# plusz-end-card-with-turnstile-mezzanine.net
KiCad netlist of a schematic drawn in EAGLE
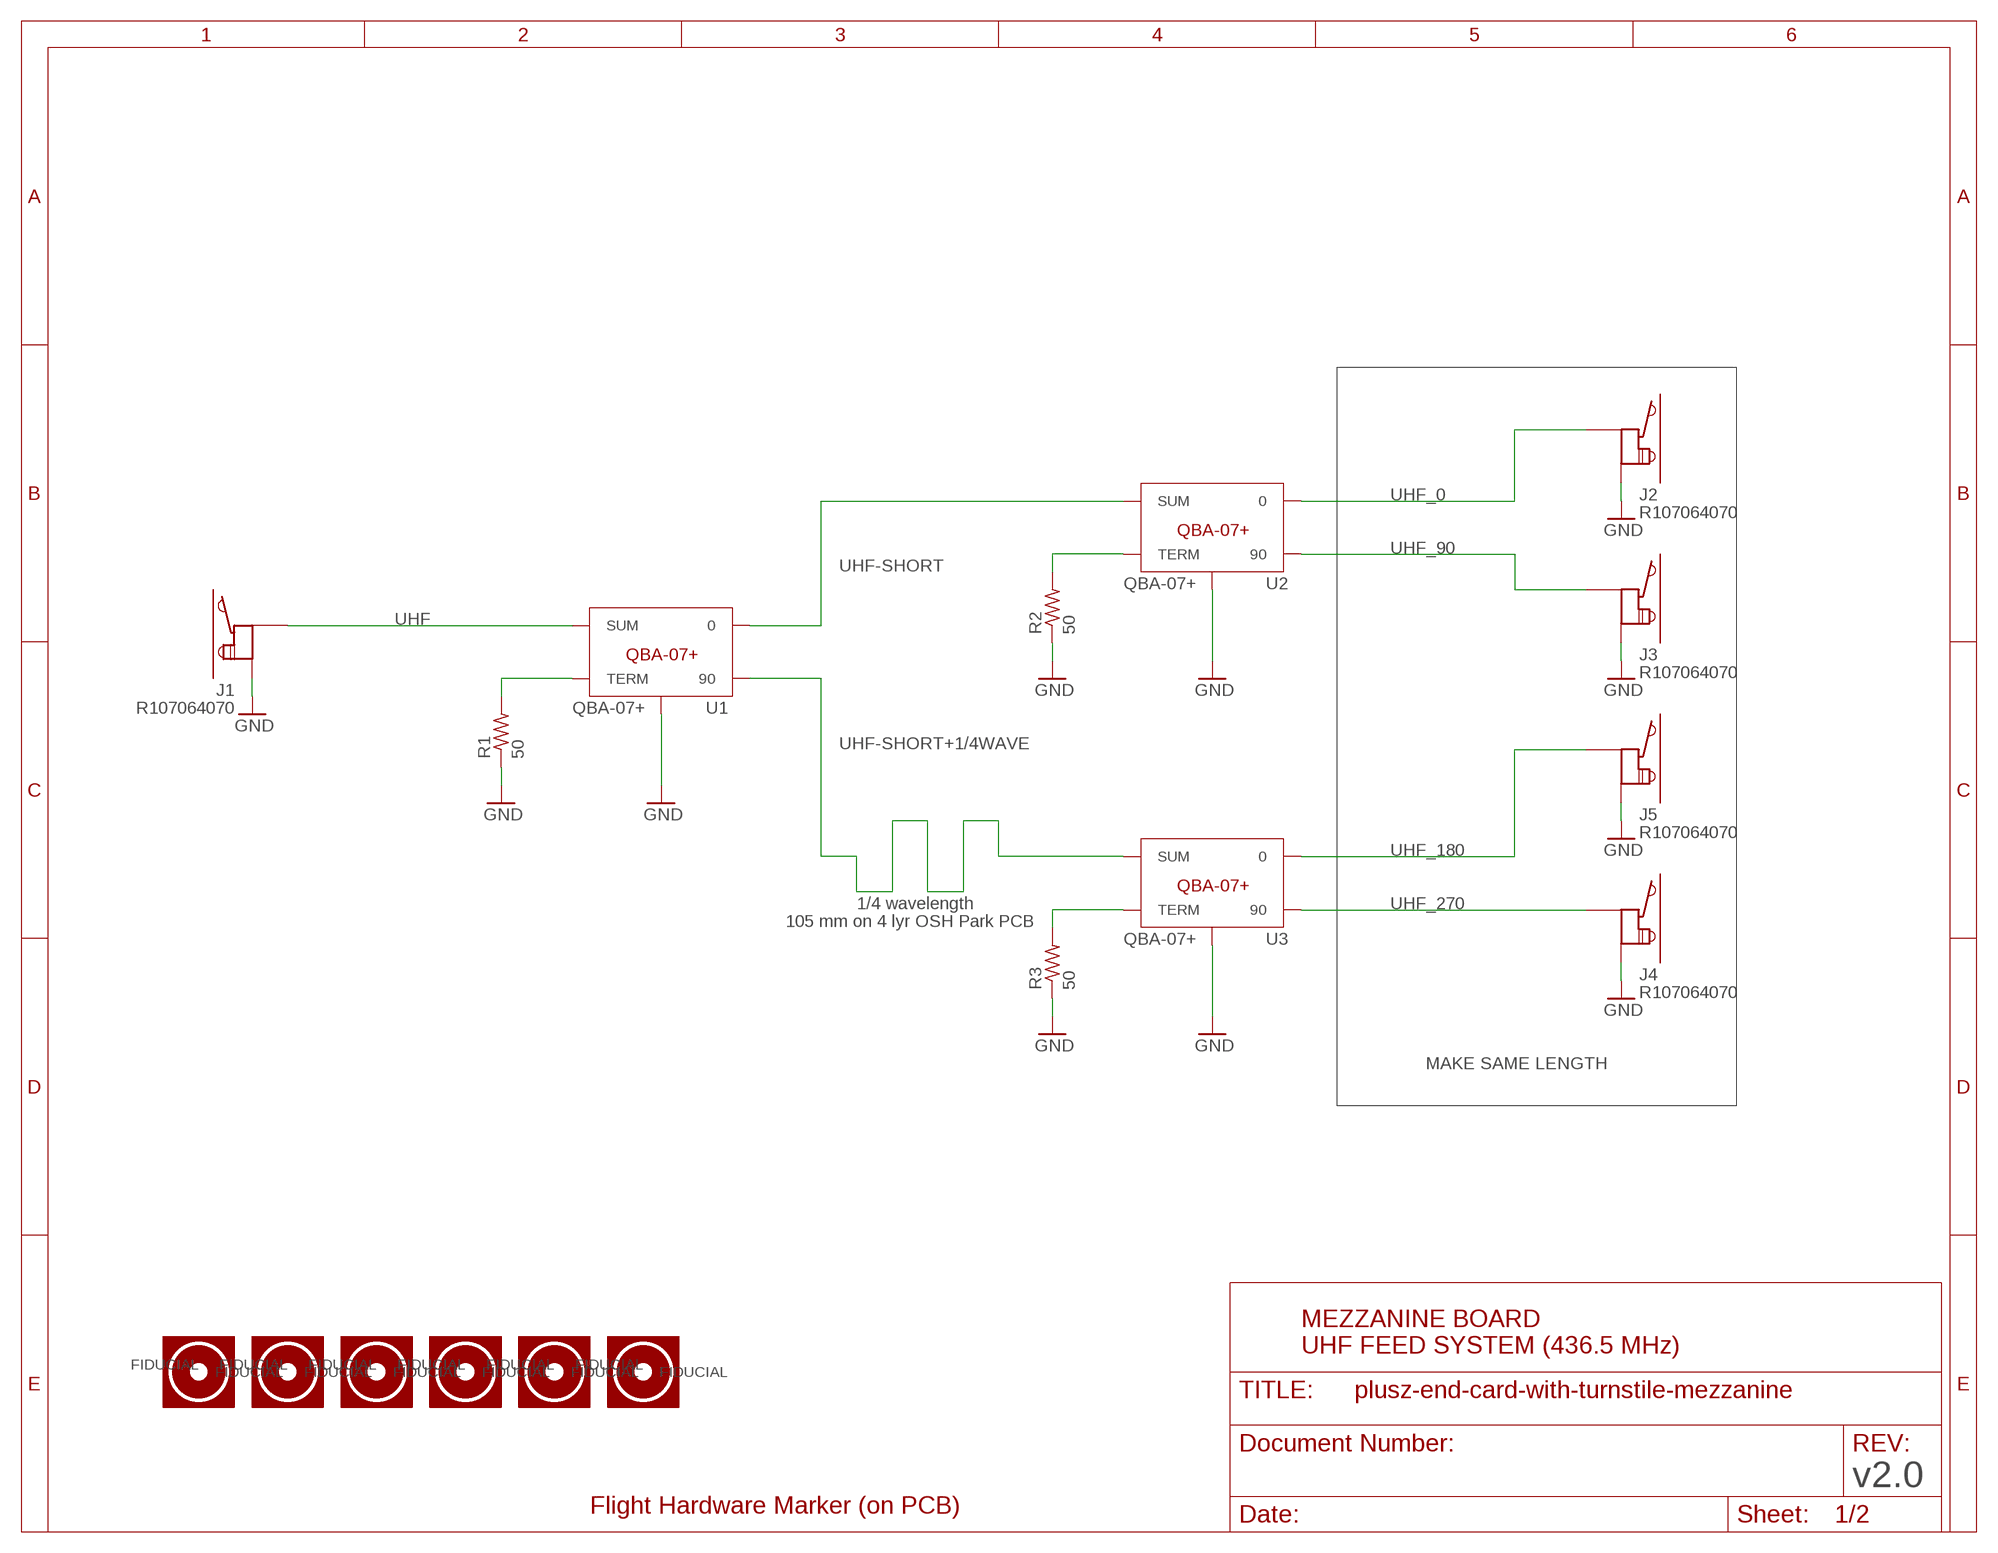
[diagram p0: schematic, sheet 1]
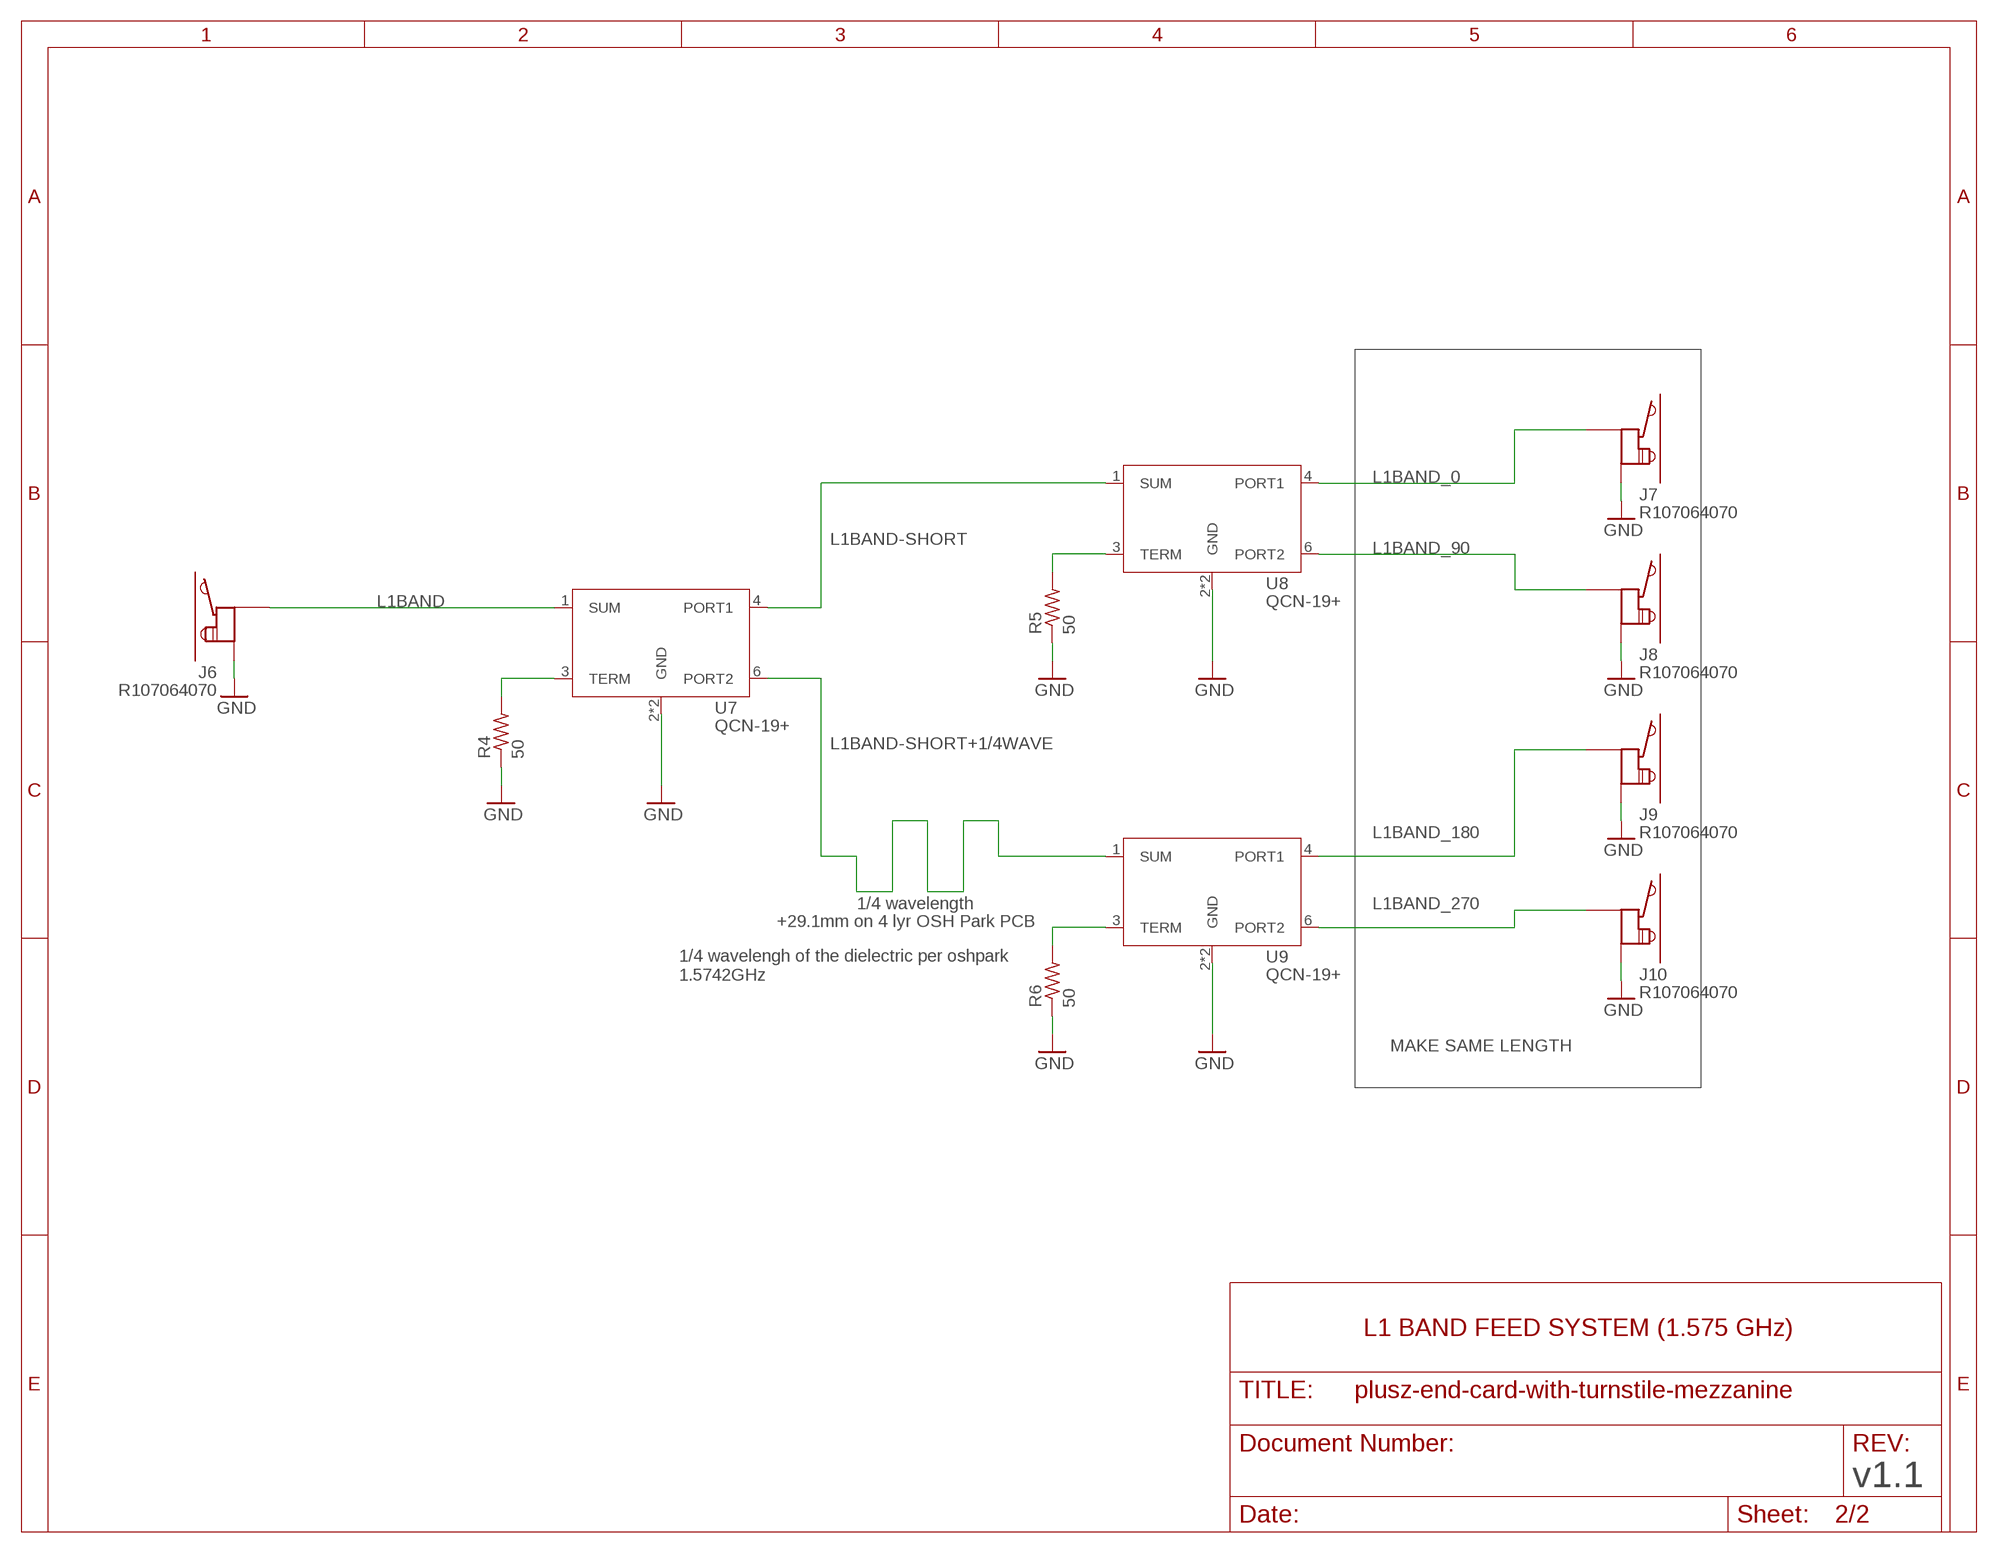
[diagram p1: schematic, sheet 2]

(export (version "E")
  (design (tool "Eeschema 10.0.6"))
  (components
    (comp (ref "J6")
      (value "R107064070")
      (footprint "eagle-import:R107064070_SOLDER")
      (fields (field (name "MFG") "Radiall"))
      (libsource (lib "eagle-import") (part "R107064070"))
    )
    (comp (ref "J7")
      (value "R107064070")
      (footprint "eagle-import:R107064070_SOLDER")
      (fields (field (name "MFG") "Radiall"))
      (libsource (lib "eagle-import") (part "R107064070"))
    )
    (comp (ref "J8")
      (value "R107064070")
      (footprint "eagle-import:R107064070_SOLDER")
      (fields (field (name "MFG") "Radiall"))
      (libsource (lib "eagle-import") (part "R107064070"))
    )
    (comp (ref "J9")
      (value "R107064070")
      (footprint "eagle-import:R107064070_SOLDER")
      (fields (field (name "MFG") "Radiall"))
      (libsource (lib "eagle-import") (part "R107064070"))
    )
    (comp (ref "J10")
      (value "R107064070")
      (footprint "eagle-import:R107064070_SOLDER")
      (fields (field (name "MFG") "Radiall"))
      (libsource (lib "eagle-import") (part "R107064070"))
    )
    (comp (ref "R4")
      (value "50")
      (footprint "eagle-import:.0603-C-NOSILK")
      (libsource (lib "eagle-import") (part "R-US_0603-C-NOSILK"))
    )
    (comp (ref "R5")
      (value "50")
      (footprint "eagle-import:.0603-C-NOSILK")
      (libsource (lib "eagle-import") (part "R-US_0603-C-NOSILK"))
    )
    (comp (ref "R6")
      (value "50")
      (footprint "eagle-import:.0603-C-NOSILK")
      (libsource (lib "eagle-import") (part "R-US_0603-C-NOSILK"))
    )
    (comp (ref "U7")
      (value "QCN-19+")
      (footprint "eagle-import:QCN-XXX+")
      (fields (field (name "MFG") "Mini-Circuits"))
      (libsource (lib "eagle-import") (part "QCN-XXX+"))
    )
    (comp (ref "U8")
      (value "QCN-19+")
      (footprint "eagle-import:QCN-XXX+")
      (fields (field (name "MFG") "Mini-Circuits"))
      (libsource (lib "eagle-import") (part "QCN-XXX+"))
    )
    (comp (ref "U9")
      (value "QCN-19+")
      (footprint "eagle-import:QCN-XXX+")
      (fields (field (name "MFG") "Mini-Circuits"))
      (libsource (lib "eagle-import") (part "QCN-XXX+"))
    )
    (comp (ref "FIDUCIAL1")
      (value "FIDUCIAL-1.0X2.0")
      (footprint "eagle-import:FIDUCIAL-1.0X2.0")
      (libsource (lib "eagle-import") (part "FIDUCIAL-1.0X2.0"))
    )
    (comp (ref "FIDUCIAL2")
      (value "FIDUCIAL-1.0X2.0")
      (footprint "eagle-import:FIDUCIAL-1.0X2.0")
      (libsource (lib "eagle-import") (part "FIDUCIAL-1.0X2.0"))
    )
    (comp (ref "FIDUCIAL3")
      (value "FIDUCIAL-1.0X2.0")
      (footprint "eagle-import:FIDUCIAL-1.0X2.0")
      (libsource (lib "eagle-import") (part "FIDUCIAL-1.0X2.0"))
    )
    (comp (ref "FIDUCIAL4")
      (value "FIDUCIAL-1.0X2.0")
      (footprint "eagle-import:FIDUCIAL-1.0X2.0")
      (libsource (lib "eagle-import") (part "FIDUCIAL-1.0X2.0"))
    )
    (comp (ref "FIDUCIAL6")
      (value "FIDUCIAL-1.0X2.0")
      (footprint "eagle-import:FIDUCIAL-1.0X2.0")
      (libsource (lib "eagle-import") (part "FIDUCIAL-1.0X2.0"))
    )
    (comp (ref "FIDUCIAL7")
      (value "FIDUCIAL-1.0X2.0")
      (footprint "eagle-import:FIDUCIAL-1.0X2.0")
      (libsource (lib "eagle-import") (part "FIDUCIAL-1.0X2.0"))
    )
    (comp (ref "J1")
      (value "R107064070")
      (footprint "eagle-import:R107064070_SOLDER")
      (fields (field (name "MFG") "Radiall"))
      (libsource (lib "eagle-import") (part "R107064070"))
    )
    (comp (ref "J2")
      (value "R107064070")
      (footprint "eagle-import:R107064070_SOLDER")
      (fields (field (name "MFG") "Radiall"))
      (libsource (lib "eagle-import") (part "R107064070"))
    )
    (comp (ref "J3")
      (value "R107064070")
      (footprint "eagle-import:R107064070_SOLDER")
      (fields (field (name "MFG") "Radiall"))
      (libsource (lib "eagle-import") (part "R107064070"))
    )
    (comp (ref "J4")
      (value "R107064070")
      (footprint "eagle-import:R107064070_SOLDER")
      (fields (field (name "MFG") "Radiall"))
      (libsource (lib "eagle-import") (part "R107064070"))
    )
    (comp (ref "J5")
      (value "R107064070")
      (footprint "eagle-import:R107064070_SOLDER")
      (fields (field (name "MFG") "Radiall"))
      (libsource (lib "eagle-import") (part "R107064070"))
    )
    (comp (ref "R1")
      (value "50")
      (footprint "eagle-import:.0603-C-NOSILK")
      (libsource (lib "eagle-import") (part "R-US_0603-C-NOSILK"))
    )
    (comp (ref "R2")
      (value "50")
      (footprint "eagle-import:.0603-C-NOSILK")
      (libsource (lib "eagle-import") (part "R-US_0603-C-NOSILK"))
    )
    (comp (ref "R3")
      (value "50")
      (footprint "eagle-import:.0603-C-NOSILK")
      (libsource (lib "eagle-import") (part "R-US_0603-C-NOSILK"))
    )
    (comp (ref "U$1")
      (value "FLIGHMARKERNEW")
      (footprint "eagle-import:FLIGHTMARKER_NEW_BOARDS")
      (libsource (lib "eagle-import") (part "FLIGHMARKERNEW"))
    )
    (comp (ref "U1")
      (value "QBA-07+")
      (footprint "eagle-import:QBA-07+")
      (libsource (lib "eagle-import") (part "QBA-07+"))
    )
    (comp (ref "U2")
      (value "QBA-07+")
      (footprint "eagle-import:QBA-07+")
      (libsource (lib "eagle-import") (part "QBA-07+"))
    )
    (comp (ref "U3")
      (value "QBA-07+")
      (footprint "eagle-import:QBA-07+")
      (libsource (lib "eagle-import") (part "QBA-07+"))
    )
  )
  (nets
    (net (code "1") (name "GND") (class "Default")
      (node (ref "J1") (pin "P$2") (pinfunction "P$2_P$2") (pintype "bidirectional"))
      (node (ref "J1") (pin "P$3") (pinfunction "P$2_P$3") (pintype "bidirectional"))
      (node (ref "J10") (pin "P$2") (pinfunction "P$2_P$2") (pintype "bidirectional"))
      (node (ref "J10") (pin "P$3") (pinfunction "P$2_P$3") (pintype "bidirectional"))
      (node (ref "J2") (pin "P$2") (pinfunction "P$2_P$2") (pintype "bidirectional"))
      (node (ref "J2") (pin "P$3") (pinfunction "P$2_P$3") (pintype "bidirectional"))
      (node (ref "J3") (pin "P$2") (pinfunction "P$2_P$2") (pintype "bidirectional"))
      (node (ref "J3") (pin "P$3") (pinfunction "P$2_P$3") (pintype "bidirectional"))
      (node (ref "J4") (pin "P$2") (pinfunction "P$2_P$2") (pintype "bidirectional"))
      (node (ref "J4") (pin "P$3") (pinfunction "P$2_P$3") (pintype "bidirectional"))
      (node (ref "J5") (pin "P$2") (pinfunction "P$2_P$2") (pintype "bidirectional"))
      (node (ref "J5") (pin "P$3") (pinfunction "P$2_P$3") (pintype "bidirectional"))
      (node (ref "J6") (pin "P$2") (pinfunction "P$2_P$2") (pintype "bidirectional"))
      (node (ref "J6") (pin "P$3") (pinfunction "P$2_P$3") (pintype "bidirectional"))
      (node (ref "J7") (pin "P$2") (pinfunction "P$2_P$2") (pintype "bidirectional"))
      (node (ref "J7") (pin "P$3") (pinfunction "P$2_P$3") (pintype "bidirectional"))
      (node (ref "J8") (pin "P$2") (pinfunction "P$2_P$2") (pintype "bidirectional"))
      (node (ref "J8") (pin "P$3") (pinfunction "P$2_P$3") (pintype "bidirectional"))
      (node (ref "J9") (pin "P$2") (pinfunction "P$2_P$2") (pintype "bidirectional"))
      (node (ref "J9") (pin "P$3") (pinfunction "P$2_P$3") (pintype "bidirectional"))
      (node (ref "R1") (pin "1") (pinfunction "1_1") (pintype "passive"))
      (node (ref "R2") (pin "1") (pinfunction "1_1") (pintype "passive"))
      (node (ref "R3") (pin "1") (pinfunction "1_1") (pintype "passive"))
      (node (ref "R4") (pin "1") (pinfunction "1_1") (pintype "passive"))
      (node (ref "R5") (pin "1") (pinfunction "1_1") (pintype "passive"))
      (node (ref "R6") (pin "1") (pinfunction "1_1") (pintype "passive"))
      (node (ref "U1") (pin "2") (pinfunction "GND_2") (pintype "power_in"))
      (node (ref "U1") (pin "3") (pinfunction "GND_3") (pintype "power_in"))
      (node (ref "U1") (pin "4") (pinfunction "GND_4") (pintype "power_in"))
      (node (ref "U1") (pin "7") (pinfunction "GND_7") (pintype "power_in"))
      (node (ref "U1") (pin "8") (pinfunction "GND_8") (pintype "power_in"))
      (node (ref "U1") (pin "9") (pinfunction "GND_9") (pintype "power_in"))
      (node (ref "U1") (pin "GND-NO-PAD") (pinfunction "GND_GND-NO-PAD") (pintype "power_in"))
      (node (ref "U2") (pin "2") (pinfunction "GND_2") (pintype "power_in"))
      (node (ref "U2") (pin "3") (pinfunction "GND_3") (pintype "power_in"))
      (node (ref "U2") (pin "4") (pinfunction "GND_4") (pintype "power_in"))
      (node (ref "U2") (pin "7") (pinfunction "GND_7") (pintype "power_in"))
      (node (ref "U2") (pin "8") (pinfunction "GND_8") (pintype "power_in"))
      (node (ref "U2") (pin "9") (pinfunction "GND_9") (pintype "power_in"))
      (node (ref "U2") (pin "GND-NO-PAD") (pinfunction "GND_GND-NO-PAD") (pintype "power_in"))
      (node (ref "U3") (pin "2") (pinfunction "GND_2") (pintype "power_in"))
      (node (ref "U3") (pin "3") (pinfunction "GND_3") (pintype "power_in"))
      (node (ref "U3") (pin "4") (pinfunction "GND_4") (pintype "power_in"))
      (node (ref "U3") (pin "7") (pinfunction "GND_7") (pintype "power_in"))
      (node (ref "U3") (pin "8") (pinfunction "GND_8") (pintype "power_in"))
      (node (ref "U3") (pin "9") (pinfunction "GND_9") (pintype "power_in"))
      (node (ref "U3") (pin "GND-NO-PAD") (pinfunction "GND_GND-NO-PAD") (pintype "power_in"))
      (node (ref "U7") (pin "2") (pinfunction "GND_2") (pintype "power_in"))
      (node (ref "U7") (pin "5") (pinfunction "GND_5") (pintype "power_in"))
      (node (ref "U8") (pin "2") (pinfunction "GND_2") (pintype "power_in"))
      (node (ref "U8") (pin "5") (pinfunction "GND_5") (pintype "power_in"))
      (node (ref "U9") (pin "2") (pinfunction "GND_2") (pintype "power_in"))
      (node (ref "U9") (pin "5") (pinfunction "GND_5") (pintype "power_in"))
    )
    (net (code "2") (name "L1BAND") (class "Default")
      (node (ref "J6") (pin "P$1") (pinfunction "P$1_P$1") (pintype "bidirectional"))
      (node (ref "U7") (pin "1") (pinfunction "SUM_1") (pintype "bidirectional"))
    )
    (net (code "3") (name "L1BAND-SHORT") (class "Default")
      (node (ref "U7") (pin "4") (pinfunction "PORT1_4") (pintype "bidirectional"))
      (node (ref "U8") (pin "1") (pinfunction "SUM_1") (pintype "bidirectional"))
    )
    (net (code "4") (name "L1BAND-SHORT+1{slash}4WAVE") (class "Default")
      (node (ref "U7") (pin "6") (pinfunction "PORT2_6") (pintype "bidirectional"))
      (node (ref "U9") (pin "1") (pinfunction "SUM_1") (pintype "bidirectional"))
    )
    (net (code "5") (name "L1BAND_0") (class "Default")
      (node (ref "J7") (pin "P$1") (pinfunction "P$1_P$1") (pintype "bidirectional"))
      (node (ref "U8") (pin "4") (pinfunction "PORT1_4") (pintype "bidirectional"))
    )
    (net (code "6") (name "L1BAND_90") (class "Default")
      (node (ref "J8") (pin "P$1") (pinfunction "P$1_P$1") (pintype "bidirectional"))
      (node (ref "U8") (pin "6") (pinfunction "PORT2_6") (pintype "bidirectional"))
    )
    (net (code "7") (name "L1BAND_180") (class "Default")
      (node (ref "J9") (pin "P$1") (pinfunction "P$1_P$1") (pintype "bidirectional"))
      (node (ref "U9") (pin "4") (pinfunction "PORT1_4") (pintype "bidirectional"))
    )
    (net (code "8") (name "L1BAND_270") (class "Default")
      (node (ref "J10") (pin "P$1") (pinfunction "P$1_P$1") (pintype "bidirectional"))
      (node (ref "U9") (pin "6") (pinfunction "PORT2_6") (pintype "bidirectional"))
    )
    (net (code "9") (name "Net-(U1-TERM)") (class "Default")
      (node (ref "R1") (pin "2") (pinfunction "2_2") (pintype "passive"))
      (node (ref "U1") (pin "5") (pinfunction "TERM_5") (pintype "passive"))
    )
    (net (code "10") (name "Net-(U2-TERM)") (class "Default")
      (node (ref "R2") (pin "2") (pinfunction "2_2") (pintype "passive"))
      (node (ref "U2") (pin "5") (pinfunction "TERM_5") (pintype "passive"))
    )
    (net (code "11") (name "Net-(U3-TERM)") (class "Default")
      (node (ref "R3") (pin "2") (pinfunction "2_2") (pintype "passive"))
      (node (ref "U3") (pin "5") (pinfunction "TERM_5") (pintype "passive"))
    )
    (net (code "12") (name "Net-(U7-TERM)") (class "Default")
      (node (ref "R4") (pin "2") (pinfunction "2_2") (pintype "passive"))
      (node (ref "U7") (pin "3") (pinfunction "TERM_3") (pintype "bidirectional"))
    )
    (net (code "13") (name "Net-(U8-TERM)") (class "Default")
      (node (ref "R5") (pin "2") (pinfunction "2_2") (pintype "passive"))
      (node (ref "U8") (pin "3") (pinfunction "TERM_3") (pintype "bidirectional"))
    )
    (net (code "14") (name "Net-(U9-TERM)") (class "Default")
      (node (ref "R6") (pin "2") (pinfunction "2_2") (pintype "passive"))
      (node (ref "U9") (pin "3") (pinfunction "TERM_3") (pintype "bidirectional"))
    )
    (net (code "15") (name "UHF") (class "Default")
      (node (ref "J1") (pin "P$1") (pinfunction "P$1_P$1") (pintype "bidirectional"))
      (node (ref "U1") (pin "1") (pinfunction "SUM_1") (pintype "passive"))
    )
    (net (code "16") (name "UHF-SHORT") (class "Default")
      (node (ref "U1") (pin "6") (pinfunction "0_6") (pintype "passive"))
      (node (ref "U2") (pin "1") (pinfunction "SUM_1") (pintype "passive"))
    )
    (net (code "17") (name "UHF-SHORT+1{slash}4WAVE") (class "Default")
      (node (ref "U1") (pin "10") (pinfunction "90_10") (pintype "passive"))
      (node (ref "U3") (pin "1") (pinfunction "SUM_1") (pintype "passive"))
    )
    (net (code "18") (name "UHF_0") (class "Default")
      (node (ref "J2") (pin "P$1") (pinfunction "P$1_P$1") (pintype "bidirectional"))
      (node (ref "U2") (pin "6") (pinfunction "0_6") (pintype "passive"))
    )
    (net (code "19") (name "UHF_90") (class "Default")
      (node (ref "J3") (pin "P$1") (pinfunction "P$1_P$1") (pintype "bidirectional"))
      (node (ref "U2") (pin "10") (pinfunction "90_10") (pintype "passive"))
    )
    (net (code "20") (name "UHF_180") (class "Default")
      (node (ref "J5") (pin "P$1") (pinfunction "P$1_P$1") (pintype "bidirectional"))
      (node (ref "U3") (pin "6") (pinfunction "0_6") (pintype "passive"))
    )
    (net (code "21") (name "UHF_270") (class "Default")
      (node (ref "J4") (pin "P$1") (pinfunction "P$1_P$1") (pintype "bidirectional"))
      (node (ref "U3") (pin "10") (pinfunction "90_10") (pintype "passive"))
    )
    (net (code "22") (name "unconnected-(FIDUCIAL1-PadFIDUCIAL)") (class "Default")
      (node (ref "FIDUCIAL1") (pin "FIDUCIAL") (pinfunction "FIDUCIAL_FIDUCIAL") (pintype "no_connect"))
    )
    (net (code "23") (name "unconnected-(FIDUCIAL2-PadFIDUCIAL)") (class "Default")
      (node (ref "FIDUCIAL2") (pin "FIDUCIAL") (pinfunction "FIDUCIAL_FIDUCIAL") (pintype "no_connect"))
    )
    (net (code "24") (name "unconnected-(FIDUCIAL3-PadFIDUCIAL)") (class "Default")
      (node (ref "FIDUCIAL3") (pin "FIDUCIAL") (pinfunction "FIDUCIAL_FIDUCIAL") (pintype "no_connect"))
    )
    (net (code "25") (name "unconnected-(FIDUCIAL4-PadFIDUCIAL)") (class "Default")
      (node (ref "FIDUCIAL4") (pin "FIDUCIAL") (pinfunction "FIDUCIAL_FIDUCIAL") (pintype "no_connect"))
    )
    (net (code "26") (name "unconnected-(FIDUCIAL6-PadFIDUCIAL)") (class "Default")
      (node (ref "FIDUCIAL6") (pin "FIDUCIAL") (pinfunction "FIDUCIAL_FIDUCIAL") (pintype "no_connect"))
    )
    (net (code "27") (name "unconnected-(FIDUCIAL7-PadFIDUCIAL)") (class "Default")
      (node (ref "FIDUCIAL7") (pin "FIDUCIAL") (pinfunction "FIDUCIAL_FIDUCIAL") (pintype "no_connect"))
    )
  )
)
